# STM32F103C.net
KiCad netlist of a schematic drawn in Altium Designer
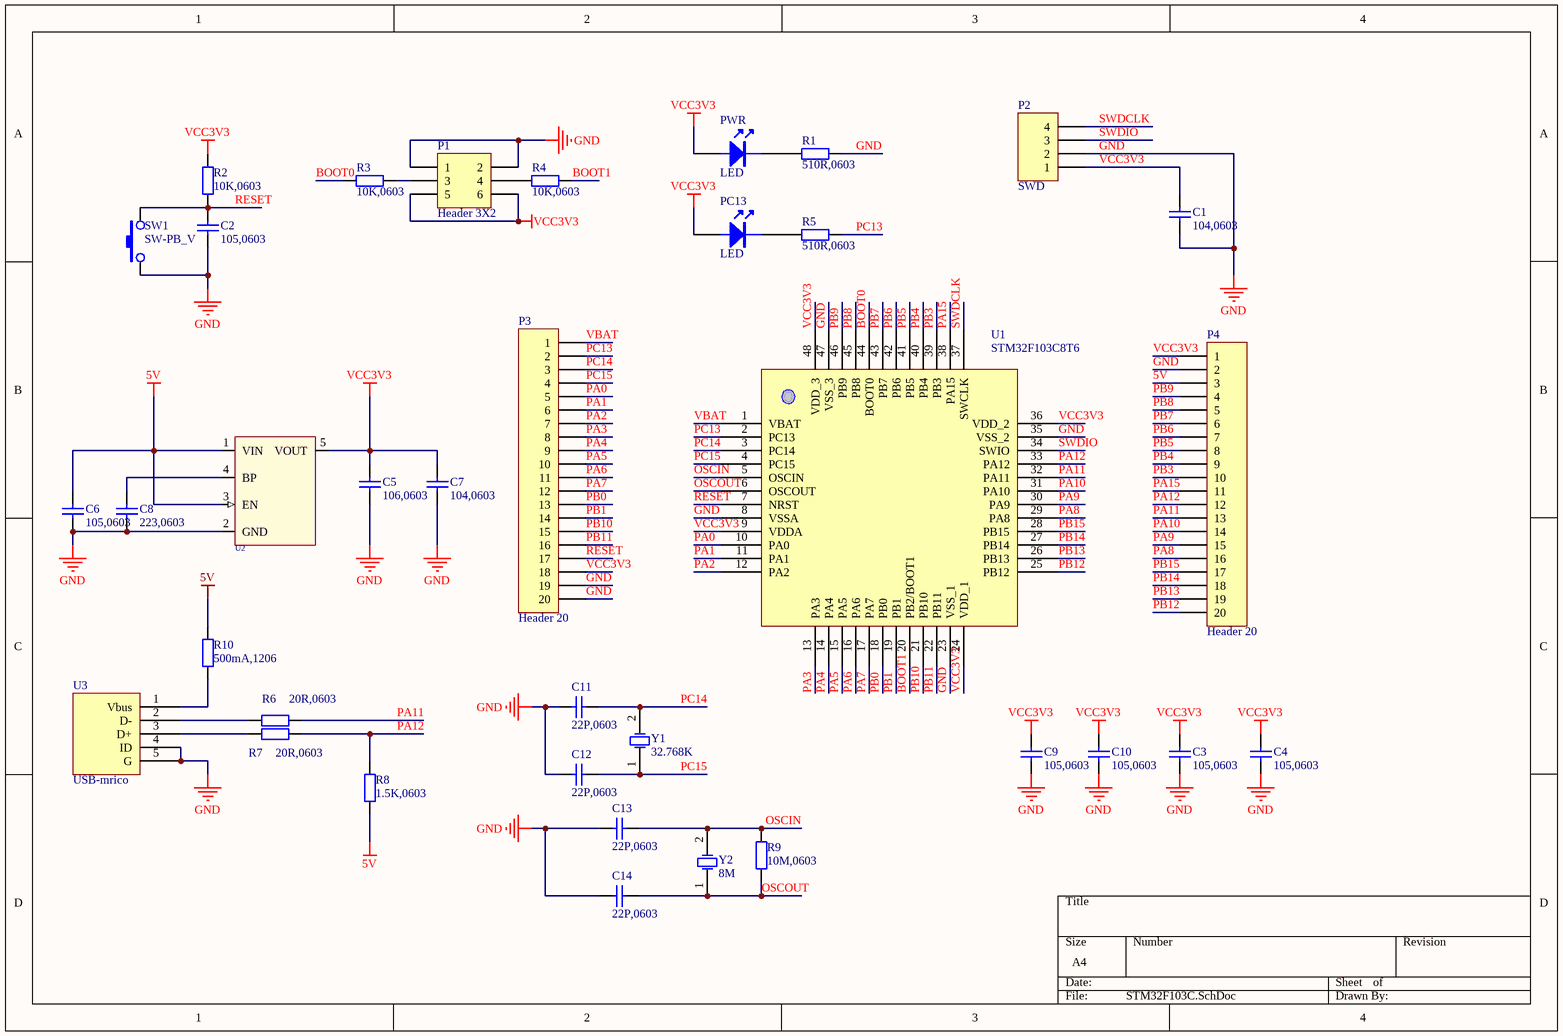
[diagram p0: STM32F103C.SchDoc]

(export (version "E")
  (design (tool "Eeschema 10.0.6"))
  (components
    (comp (ref "C1")
      (value "104,0603")
      (footprint "C 0603")
      (description "Capacitor")
      (fields (field (name "PUBLISHER") "Altium Limited"))
      (libsource (lib "STM32F103C8T6") (part "Cap"))
    )
    (comp (ref "C2")
      (value "105,0603")
      (footprint "C 0603")
      (description "Capacitor")
      (fields (field (name "PUBLISHER") "Altium Limited"))
      (libsource (lib "STM32F103C8T6") (part "Cap"))
    )
    (comp (ref "C3")
      (value "105,0603")
      (footprint "C 0603")
      (description "Capacitor")
      (fields (field (name "PUBLISHER") "Altium Limited"))
      (libsource (lib "STM32F103C8T6") (part "Cap"))
    )
    (comp (ref "C4")
      (value "105,0603")
      (footprint "C 0603")
      (description "Capacitor")
      (fields (field (name "PUBLISHER") "Altium Limited"))
      (libsource (lib "STM32F103C8T6") (part "Cap"))
    )
    (comp (ref "C5")
      (value "106,0603")
      (footprint "C 0603")
      (description "Capacitor")
      (fields (field (name "PUBLISHER") "Altium Limited"))
      (libsource (lib "STM32F103C8T6") (part "Cap"))
    )
    (comp (ref "C6")
      (value "105,0603")
      (footprint "C 0603")
      (description "Capacitor")
      (fields (field (name "PUBLISHER") "Altium Limited"))
      (libsource (lib "STM32F103C8T6") (part "Cap"))
    )
    (comp (ref "C7")
      (value "104,0603")
      (footprint "C 0603")
      (description "Capacitor")
      (fields (field (name "PUBLISHER") "Altium Limited"))
      (libsource (lib "STM32F103C8T6") (part "Cap"))
    )
    (comp (ref "C8")
      (value "223,0603")
      (footprint "C 0603")
      (description "Capacitor")
      (fields (field (name "PUBLISHER") "Altium Limited"))
      (libsource (lib "STM32F103C8T6") (part "Cap"))
    )
    (comp (ref "C9")
      (value "105,0603")
      (footprint "C 0603")
      (description "Capacitor")
      (fields (field (name "PUBLISHER") "Altium Limited"))
      (libsource (lib "STM32F103C8T6") (part "Cap"))
    )
    (comp (ref "C10")
      (value "105,0603")
      (footprint "C 0603")
      (description "Capacitor")
      (fields (field (name "PUBLISHER") "Altium Limited"))
      (libsource (lib "STM32F103C8T6") (part "Cap"))
    )
    (comp (ref "C11")
      (value "22P,0603")
      (footprint "C 0603")
      (description "Capacitor")
      (fields (field (name "PUBLISHER") "Altium Limited"))
      (libsource (lib "STM32F103C8T6") (part "Cap"))
    )
    (comp (ref "C12")
      (value "22P,0603")
      (footprint "C 0603")
      (description "Capacitor")
      (fields (field (name "PUBLISHER") "Altium Limited"))
      (libsource (lib "STM32F103C8T6") (part "Cap"))
    )
    (comp (ref "C13")
      (value "22P,0603")
      (footprint "C 0603")
      (description "Capacitor")
      (fields (field (name "PUBLISHER") "Altium Limited"))
      (libsource (lib "STM32F103C8T6") (part "Cap"))
    )
    (comp (ref "C14")
      (value "22P,0603")
      (footprint "C 0603")
      (description "Capacitor")
      (fields (field (name "PUBLISHER") "Altium Limited"))
      (libsource (lib "STM32F103C8T6") (part "Cap"))
    )
    (comp (ref "P1")
      (value "Header 3X2")
      (footprint "HDR-3X2")
      (description "Header, 3-Pin, Dual row")
      (fields (field (name "PUBLISHER") "Altium Limited"))
      (libsource (lib "STM32F103C8T6") (part "Header 3X2"))
    )
    (comp (ref "P2")
      (value "SWD")
      (footprint "HDR-1X4_H")
      (description "Header, 4-Pin")
      (fields (field (name "PUBLISHER") "Altium Limited"))
      (libsource (lib "STM32F103C8T6") (part "Header 4"))
    )
    (comp (ref "P3")
      (value "Header 20")
      (footprint "HDR1X20")
      (description "Header, 20-Pin")
      (fields (field (name "PUBLISHER") "Altium Limited"))
      (libsource (lib "STM32F103C8T6") (part "Header 20"))
    )
    (comp (ref "P4")
      (value "Header 20")
      (footprint "HDR1X20")
      (description "Header, 20-Pin")
      (fields (field (name "PUBLISHER") "Altium Limited"))
      (libsource (lib "") (part "Header 20_1"))
    )
    (comp (ref "PC13") (value "LED") (footprint "LED 0805G") (libsource (lib "STM32F103C8T6") (part "LED")))
    (comp (ref "PWR") (value "LED") (footprint "LED 0805G") (libsource (lib "STM32F103C8T6") (part "LED")))
    (comp (ref "R1")
      (value "510R,0603")
      (footprint "R 0603")
      (description "Resistor")
      (fields (field (name "PUBLISHER") "Altium Limited"))
      (libsource (lib "STM32F103C8T6") (part "Res2"))
    )
    (comp (ref "R2")
      (value "10K,0603")
      (footprint "R 0603")
      (description "Resistor")
      (fields (field (name "PUBLISHER") "Altium Limited"))
      (libsource (lib "") (part "Res2_1"))
    )
    (comp (ref "R3")
      (value "10K,0603")
      (footprint "R 0603")
      (description "Resistor")
      (fields (field (name "PUBLISHER") "Altium Limited"))
      (libsource (lib "STM32F103C8T6") (part "Res2"))
    )
    (comp (ref "R4")
      (value "10K,0603")
      (footprint "R 0603")
      (description "Resistor")
      (fields (field (name "PUBLISHER") "Altium Limited"))
      (libsource (lib "STM32F103C8T6") (part "Res2"))
    )
    (comp (ref "R5")
      (value "510R,0603")
      (footprint "R 0603")
      (description "Resistor")
      (fields (field (name "PUBLISHER") "Altium Limited"))
      (libsource (lib "STM32F103C8T6") (part "Res2"))
    )
    (comp (ref "R6")
      (value "20R,0603")
      (footprint "R 0603")
      (description "Resistor")
      (fields (field (name "PUBLISHER") "Altium Limited"))
      (libsource (lib "STM32F103C8T6") (part "Res2"))
    )
    (comp (ref "R7")
      (value "20R,0603")
      (footprint "R 0603")
      (description "Resistor")
      (fields (field (name "PUBLISHER") "Altium Limited"))
      (libsource (lib "STM32F103C8T6") (part "Res2"))
    )
    (comp (ref "R8")
      (value "1.5K,0603")
      (footprint "R 0603")
      (description "Resistor")
      (fields (field (name "PUBLISHER") "Altium Limited"))
      (libsource (lib "") (part "Res2_1"))
    )
    (comp (ref "R9")
      (value "10M,0603")
      (footprint "R 0603")
      (description "Resistor")
      (fields (field (name "PUBLISHER") "Altium Limited"))
      (libsource (lib "") (part "Res2_1"))
    )
    (comp (ref "R10")
      (value "500mA,1206")
      (footprint "R 1206")
      (description "Fuse")
      (fields (field (name "PUBLISHER") "Altium Limited"))
      (libsource (lib "PCB_Project_4") (part "Fuse"))
    )
    (comp (ref "SW1")
      (value "SW-PB_V")
      (footprint "TSW SMD-3*6*2.5")
      (description "SWITCH")
      (libsource (lib "STM32F103C8T6") (part "SW-PB_V"))
    )
    (comp (ref "U1")
      (value "STM32F103C8T6")
      (footprint "TQFP48 7x7_L")
      (libsource (lib "STM32F103C8T6") (part "STM32F103C8T6"))
    )
    (comp (ref "U2")
      (value "RT9193")
      (footprint "SOT23-5L")
      (fields (field (name "ICA_PARTNUM") "$$2191094$$RT9193-15CU5") (field (name "PART NUMBER") "TMP-13"))
      (libsource (lib "STM32F103C8T6") (part "RT9193X_5P"))
    )
    (comp (ref "U3")
      (value "USB-mrico")
      (footprint "USB-micro_B")
      (libsource (lib "PCB_Project_4") (part "usb-STM"))
    )
    (comp (ref "Y1")
      (value "32.768K")
      (footprint "XTAL-3215")
      (description "Crystal Oscillator")
      (fields (field (name "PUBLISHER") "Altium Limited"))
      (libsource (lib "PCB_Project_4") (part "XTAL"))
    )
    (comp (ref "Y2")
      (value "8M")
      (footprint "STM32F103C8T6核心板:XTAL-5032")
      (description "Crystal Oscillator")
      (fields (field (name "PUBLISHER") "Altium Limited"))
      (libsource (lib "PCB_Project_4") (part "XTAL"))
    )
  )
  (nets
    (net (code "1") (name "/BOOT0") (class "Default")
      (node (ref "R3") (pin "1") (pinfunction "1_1") (pintype "passive"))
      (node (ref "U1") (pin "44") (pinfunction "BOOT0_44") (pintype "passive"))
    )
    (net (code "2") (name "/BOOT1") (class "Default")
      (node (ref "R4") (pin "2") (pinfunction "2_2") (pintype "passive"))
      (node (ref "U1") (pin "20") (pinfunction "PB2/BOOT1_20") (pintype "passive"))
    )
    (net (code "3") (name "/OSCIN") (class "Default")
      (node (ref "C13") (pin "1") (pinfunction "1_1") (pintype "passive"))
      (node (ref "R9") (pin "2") (pinfunction "2_2") (pintype "passive"))
      (node (ref "U1") (pin "5") (pinfunction "OSCIN_5") (pintype "passive"))
      (node (ref "Y2") (pin "2") (pinfunction "OSC2_2") (pintype "passive"))
    )
    (net (code "4") (name "/OSCOUT") (class "Default")
      (node (ref "C14") (pin "1") (pinfunction "1_1") (pintype "passive"))
      (node (ref "R9") (pin "1") (pinfunction "1_1") (pintype "passive"))
      (node (ref "U1") (pin "6") (pinfunction "OSCOUT_6") (pintype "passive"))
      (node (ref "Y2") (pin "1") (pinfunction "OSC1_1") (pintype "passive"))
    )
    (net (code "5") (name "/PA0") (class "Default")
      (node (ref "P3") (pin "5") (pinfunction "5_5") (pintype "passive"))
      (node (ref "U1") (pin "10") (pinfunction "PA0_10") (pintype "passive"))
    )
    (net (code "6") (name "/PA1") (class "Default")
      (node (ref "P3") (pin "6") (pinfunction "6_6") (pintype "passive"))
      (node (ref "U1") (pin "11") (pinfunction "PA1_11") (pintype "passive"))
    )
    (net (code "7") (name "/PA2") (class "Default")
      (node (ref "P3") (pin "7") (pinfunction "7_7") (pintype "passive"))
      (node (ref "U1") (pin "12") (pinfunction "PA2_12") (pintype "passive"))
    )
    (net (code "8") (name "/PA3") (class "Default")
      (node (ref "P3") (pin "8") (pinfunction "8_8") (pintype "passive"))
      (node (ref "U1") (pin "13") (pinfunction "PA3_13") (pintype "passive"))
    )
    (net (code "9") (name "/PA4") (class "Default")
      (node (ref "P3") (pin "9") (pinfunction "9_9") (pintype "passive"))
      (node (ref "U1") (pin "14") (pinfunction "PA4_14") (pintype "passive"))
    )
    (net (code "10") (name "/PA5") (class "Default")
      (node (ref "P3") (pin "10") (pinfunction "10_10") (pintype "passive"))
      (node (ref "U1") (pin "15") (pinfunction "PA5_15") (pintype "passive"))
    )
    (net (code "11") (name "/PA6") (class "Default")
      (node (ref "P3") (pin "11") (pinfunction "11_11") (pintype "passive"))
      (node (ref "U1") (pin "16") (pinfunction "PA6_16") (pintype "passive"))
    )
    (net (code "12") (name "/PA7") (class "Default")
      (node (ref "P3") (pin "12") (pinfunction "12_12") (pintype "passive"))
      (node (ref "U1") (pin "17") (pinfunction "PA7_17") (pintype "passive"))
    )
    (net (code "13") (name "/PA8") (class "Default")
      (node (ref "P4") (pin "16") (pinfunction "16_16") (pintype "passive"))
      (node (ref "U1") (pin "29") (pinfunction "PA8_29") (pintype "passive"))
    )
    (net (code "14") (name "/PA9") (class "Default")
      (node (ref "P4") (pin "15") (pinfunction "15_15") (pintype "passive"))
      (node (ref "U1") (pin "30") (pinfunction "PA9_30") (pintype "passive"))
    )
    (net (code "15") (name "/PA10") (class "Default")
      (node (ref "P4") (pin "14") (pinfunction "14_14") (pintype "passive"))
      (node (ref "U1") (pin "31") (pinfunction "PA10_31") (pintype "passive"))
    )
    (net (code "16") (name "/PA11") (class "Default")
      (node (ref "P4") (pin "13") (pinfunction "13_13") (pintype "passive"))
      (node (ref "R6") (pin "2") (pinfunction "2_2") (pintype "passive"))
      (node (ref "U1") (pin "32") (pinfunction "PA11_32") (pintype "passive"))
    )
    (net (code "17") (name "/PA12") (class "Default")
      (node (ref "P4") (pin "12") (pinfunction "12_12") (pintype "passive"))
      (node (ref "R7") (pin "2") (pinfunction "2_2") (pintype "passive"))
      (node (ref "R8") (pin "2") (pinfunction "2_2") (pintype "passive"))
      (node (ref "U1") (pin "33") (pinfunction "PA12_33") (pintype "passive"))
    )
    (net (code "18") (name "/PA15") (class "Default")
      (node (ref "P4") (pin "11") (pinfunction "11_11") (pintype "passive"))
      (node (ref "U1") (pin "38") (pinfunction "PA15_38") (pintype "passive"))
    )
    (net (code "19") (name "/PB0") (class "Default")
      (node (ref "P3") (pin "13") (pinfunction "13_13") (pintype "passive"))
      (node (ref "U1") (pin "18") (pinfunction "PB0_18") (pintype "passive"))
    )
    (net (code "20") (name "/PB1") (class "Default")
      (node (ref "P3") (pin "14") (pinfunction "14_14") (pintype "passive"))
      (node (ref "U1") (pin "19") (pinfunction "PB1_19") (pintype "passive"))
    )
    (net (code "21") (name "/PB3") (class "Default")
      (node (ref "P4") (pin "10") (pinfunction "10_10") (pintype "passive"))
      (node (ref "U1") (pin "39") (pinfunction "PB3_39") (pintype "passive"))
    )
    (net (code "22") (name "/PB4") (class "Default")
      (node (ref "P4") (pin "9") (pinfunction "9_9") (pintype "passive"))
      (node (ref "U1") (pin "40") (pinfunction "PB4_40") (pintype "passive"))
    )
    (net (code "23") (name "/PB5") (class "Default")
      (node (ref "P4") (pin "8") (pinfunction "8_8") (pintype "passive"))
      (node (ref "U1") (pin "41") (pinfunction "PB5_41") (pintype "passive"))
    )
    (net (code "24") (name "/PB6") (class "Default")
      (node (ref "P4") (pin "7") (pinfunction "7_7") (pintype "passive"))
      (node (ref "U1") (pin "42") (pinfunction "PB6_42") (pintype "passive"))
    )
    (net (code "25") (name "/PB7") (class "Default")
      (node (ref "P4") (pin "6") (pinfunction "6_6") (pintype "passive"))
      (node (ref "U1") (pin "43") (pinfunction "PB7_43") (pintype "passive"))
    )
    (net (code "26") (name "/PB8") (class "Default")
      (node (ref "P4") (pin "5") (pinfunction "5_5") (pintype "passive"))
      (node (ref "U1") (pin "45") (pinfunction "PB8_45") (pintype "passive"))
    )
    (net (code "27") (name "/PB9") (class "Default")
      (node (ref "P4") (pin "4") (pinfunction "4_4") (pintype "passive"))
      (node (ref "U1") (pin "46") (pinfunction "PB9_46") (pintype "passive"))
    )
    (net (code "28") (name "/PB10") (class "Default")
      (node (ref "P3") (pin "15") (pinfunction "15_15") (pintype "passive"))
      (node (ref "U1") (pin "21") (pinfunction "PB10_21") (pintype "passive"))
    )
    (net (code "29") (name "/PB11") (class "Default")
      (node (ref "P3") (pin "16") (pinfunction "16_16") (pintype "passive"))
      (node (ref "U1") (pin "22") (pinfunction "PB11_22") (pintype "passive"))
    )
    (net (code "30") (name "/PB12") (class "Default")
      (node (ref "P4") (pin "20") (pinfunction "20_20") (pintype "passive"))
      (node (ref "U1") (pin "25") (pinfunction "PB12_25") (pintype "passive"))
    )
    (net (code "31") (name "/PB13") (class "Default")
      (node (ref "P4") (pin "19") (pinfunction "19_19") (pintype "passive"))
      (node (ref "U1") (pin "26") (pinfunction "PB13_26") (pintype "passive"))
    )
    (net (code "32") (name "/PB14") (class "Default")
      (node (ref "P4") (pin "18") (pinfunction "18_18") (pintype "passive"))
      (node (ref "U1") (pin "27") (pinfunction "PB14_27") (pintype "passive"))
    )
    (net (code "33") (name "/PB15") (class "Default")
      (node (ref "P4") (pin "17") (pinfunction "17_17") (pintype "passive"))
      (node (ref "U1") (pin "28") (pinfunction "PB15_28") (pintype "passive"))
    )
    (net (code "34") (name "/PC13") (class "Default")
      (node (ref "P3") (pin "2") (pinfunction "2_2") (pintype "passive"))
      (node (ref "R5") (pin "2") (pinfunction "2_2") (pintype "passive"))
      (node (ref "U1") (pin "2") (pinfunction "PC13_2") (pintype "passive"))
    )
    (net (code "35") (name "/PC14") (class "Default")
      (node (ref "C11") (pin "1") (pinfunction "1_1") (pintype "passive"))
      (node (ref "P3") (pin "3") (pinfunction "3_3") (pintype "passive"))
      (node (ref "U1") (pin "3") (pinfunction "PC14_3") (pintype "passive"))
      (node (ref "Y1") (pin "2") (pinfunction "OSC2_2") (pintype "passive"))
    )
    (net (code "36") (name "/PC15") (class "Default")
      (node (ref "C12") (pin "1") (pinfunction "1_1") (pintype "passive"))
      (node (ref "P3") (pin "4") (pinfunction "4_4") (pintype "passive"))
      (node (ref "U1") (pin "4") (pinfunction "PC15_4") (pintype "passive"))
      (node (ref "Y1") (pin "1") (pinfunction "OSC1_1") (pintype "passive"))
    )
    (net (code "37") (name "/RESET") (class "Default")
      (node (ref "C2") (pin "2") (pinfunction "2_2") (pintype "passive"))
      (node (ref "P3") (pin "17") (pinfunction "17_17") (pintype "passive"))
      (node (ref "R2") (pin "1") (pinfunction "1_1") (pintype "passive"))
      (node (ref "SW1") (pin "2") (pinfunction "2_2") (pintype "passive"))
      (node (ref "U1") (pin "7") (pinfunction "NRST_7") (pintype "passive"))
    )
    (net (code "38") (name "/SWDCLK") (class "Default")
      (node (ref "P2") (pin "4") (pinfunction "4_4") (pintype "passive"))
      (node (ref "U1") (pin "37") (pinfunction "SWCLK_37") (pintype "passive"))
    )
    (net (code "39") (name "/SWDIO") (class "Default")
      (node (ref "P2") (pin "3") (pinfunction "3_3") (pintype "passive"))
      (node (ref "U1") (pin "34") (pinfunction "SWIO_34") (pintype "passive"))
    )
    (net (code "40") (name "/VBAT") (class "Default")
      (node (ref "P3") (pin "1") (pinfunction "1_1") (pintype "passive"))
      (node (ref "U1") (pin "1") (pinfunction "VBAT_1") (pintype "passive"))
    )
    (net (code "41") (name "5V") (class "Default")
      (node (ref "C6") (pin "2") (pinfunction "2_2") (pintype "passive"))
      (node (ref "P4") (pin "3") (pinfunction "3_3") (pintype "passive"))
      (node (ref "R10") (pin "2") (pinfunction "2_2") (pintype "passive"))
      (node (ref "R8") (pin "1") (pinfunction "1_1") (pintype "passive"))
      (node (ref "U2") (pin "1") (pinfunction "VIN_1") (pintype "power_in"))
      (node (ref "U2") (pin "3") (pinfunction "EN_3") (pintype "input"))
    )
    (net (code "42") (name "GND") (class "Default")
      (node (ref "C1") (pin "1") (pinfunction "1_1") (pintype "passive"))
      (node (ref "C10") (pin "1") (pinfunction "1_1") (pintype "passive"))
      (node (ref "C11") (pin "2") (pinfunction "2_2") (pintype "passive"))
      (node (ref "C12") (pin "2") (pinfunction "2_2") (pintype "passive"))
      (node (ref "C13") (pin "2") (pinfunction "2_2") (pintype "passive"))
      (node (ref "C14") (pin "2") (pinfunction "2_2") (pintype "passive"))
      (node (ref "C2") (pin "1") (pinfunction "1_1") (pintype "passive"))
      (node (ref "C3") (pin "1") (pinfunction "1_1") (pintype "passive"))
      (node (ref "C4") (pin "1") (pinfunction "1_1") (pintype "passive"))
      (node (ref "C5") (pin "2") (pinfunction "2_2") (pintype "passive"))
      (node (ref "C6") (pin "1") (pinfunction "1_1") (pintype "passive"))
      (node (ref "C7") (pin "1") (pinfunction "1_1") (pintype "passive"))
      (node (ref "C8") (pin "1") (pinfunction "1_1") (pintype "passive"))
      (node (ref "C9") (pin "1") (pinfunction "1_1") (pintype "passive"))
      (node (ref "P1") (pin "1") (pinfunction "1_1") (pintype "passive"))
      (node (ref "P1") (pin "2") (pinfunction "2_2") (pintype "passive"))
      (node (ref "P2") (pin "2") (pinfunction "2_2") (pintype "passive"))
      (node (ref "P3") (pin "19") (pinfunction "19_19") (pintype "passive"))
      (node (ref "P3") (pin "20") (pinfunction "20_20") (pintype "passive"))
      (node (ref "P4") (pin "2") (pinfunction "2_2") (pintype "passive"))
      (node (ref "R1") (pin "2") (pinfunction "2_2") (pintype "passive"))
      (node (ref "SW1") (pin "1") (pinfunction "1_1") (pintype "passive"))
      (node (ref "U1") (pin "23") (pinfunction "VSS_1_23") (pintype "passive"))
      (node (ref "U1") (pin "35") (pinfunction "VSS_2_35") (pintype "passive"))
      (node (ref "U1") (pin "47") (pinfunction "VSS_3_47") (pintype "passive"))
      (node (ref "U1") (pin "8") (pinfunction "VSSA_8") (pintype "passive"))
      (node (ref "U2") (pin "2") (pinfunction "GND_2") (pintype "power_in"))
      (node (ref "U3") (pin "4") (pinfunction "ID_4") (pintype "passive"))
      (node (ref "U3") (pin "5") (pinfunction "G_5") (pintype "passive"))
    )
    (net (code "43") (name "Net-(P1-Pad3)") (class "Default")
      (node (ref "P1") (pin "3") (pinfunction "3_3") (pintype "passive"))
      (node (ref "R3") (pin "2") (pinfunction "2_2") (pintype "passive"))
    )
    (net (code "44") (name "Net-(P1-Pad4)") (class "Default")
      (node (ref "P1") (pin "4") (pinfunction "4_4") (pintype "passive"))
      (node (ref "R4") (pin "1") (pinfunction "1_1") (pintype "passive"))
    )
    (net (code "45") (name "Net-(PC13-Pad2)") (class "Default")
      (node (ref "PC13") (pin "2") (pinfunction "2_2") (pintype "passive"))
      (node (ref "R5") (pin "1") (pinfunction "1_1") (pintype "passive"))
    )
    (net (code "46") (name "Net-(PWR-Pad2)") (class "Default")
      (node (ref "PWR") (pin "2") (pinfunction "2_2") (pintype "passive"))
      (node (ref "R1") (pin "1") (pinfunction "1_1") (pintype "passive"))
    )
    (net (code "47") (name "Net-(U2-BP)") (class "Default")
      (node (ref "C8") (pin "2") (pinfunction "2_2") (pintype "passive"))
      (node (ref "U2") (pin "4") (pinfunction "BP_4") (pintype "passive"))
    )
    (net (code "48") (name "Net-(U3-D+)") (class "Default")
      (node (ref "R7") (pin "1") (pinfunction "1_1") (pintype "passive"))
      (node (ref "U3") (pin "3") (pinfunction "D+_3") (pintype "passive"))
    )
    (net (code "49") (name "Net-(U3-D-)") (class "Default")
      (node (ref "R6") (pin "1") (pinfunction "1_1") (pintype "passive"))
      (node (ref "U3") (pin "2") (pinfunction "D-_2") (pintype "passive"))
    )
    (net (code "50") (name "Net-(U3-Vbus)") (class "Default")
      (node (ref "R10") (pin "1") (pinfunction "1_1") (pintype "passive"))
      (node (ref "U3") (pin "1") (pinfunction "Vbus_1") (pintype "passive"))
    )
    (net (code "51") (name "VCC3V3") (class "Default")
      (node (ref "C1") (pin "2") (pinfunction "2_2") (pintype "passive"))
      (node (ref "C10") (pin "2") (pinfunction "2_2") (pintype "passive"))
      (node (ref "C3") (pin "2") (pinfunction "2_2") (pintype "passive"))
      (node (ref "C4") (pin "2") (pinfunction "2_2") (pintype "passive"))
      (node (ref "C5") (pin "1") (pinfunction "1_1") (pintype "passive"))
      (node (ref "C7") (pin "2") (pinfunction "2_2") (pintype "passive"))
      (node (ref "C9") (pin "2") (pinfunction "2_2") (pintype "passive"))
      (node (ref "P1") (pin "5") (pinfunction "5_5") (pintype "passive"))
      (node (ref "P1") (pin "6") (pinfunction "6_6") (pintype "passive"))
      (node (ref "P2") (pin "1") (pinfunction "1_1") (pintype "passive"))
      (node (ref "P3") (pin "18") (pinfunction "18_18") (pintype "passive"))
      (node (ref "P4") (pin "1") (pinfunction "1_1") (pintype "passive"))
      (node (ref "PC13") (pin "1") (pinfunction "1_1") (pintype "passive"))
      (node (ref "PWR") (pin "1") (pinfunction "1_1") (pintype "passive"))
      (node (ref "R2") (pin "2") (pinfunction "2_2") (pintype "passive"))
      (node (ref "U1") (pin "24") (pinfunction "VDD_1_24") (pintype "passive"))
      (node (ref "U1") (pin "36") (pinfunction "VDD_2_36") (pintype "passive"))
      (node (ref "U1") (pin "48") (pinfunction "VDD_3_48") (pintype "passive"))
      (node (ref "U1") (pin "9") (pinfunction "VDDA_9") (pintype "passive"))
      (node (ref "U2") (pin "5") (pinfunction "VOUT_5") (pintype "power_in"))
    )
  )
)
